# Human_Harp_Player.net
KiCad netlist of a schematic drawn in EAGLE
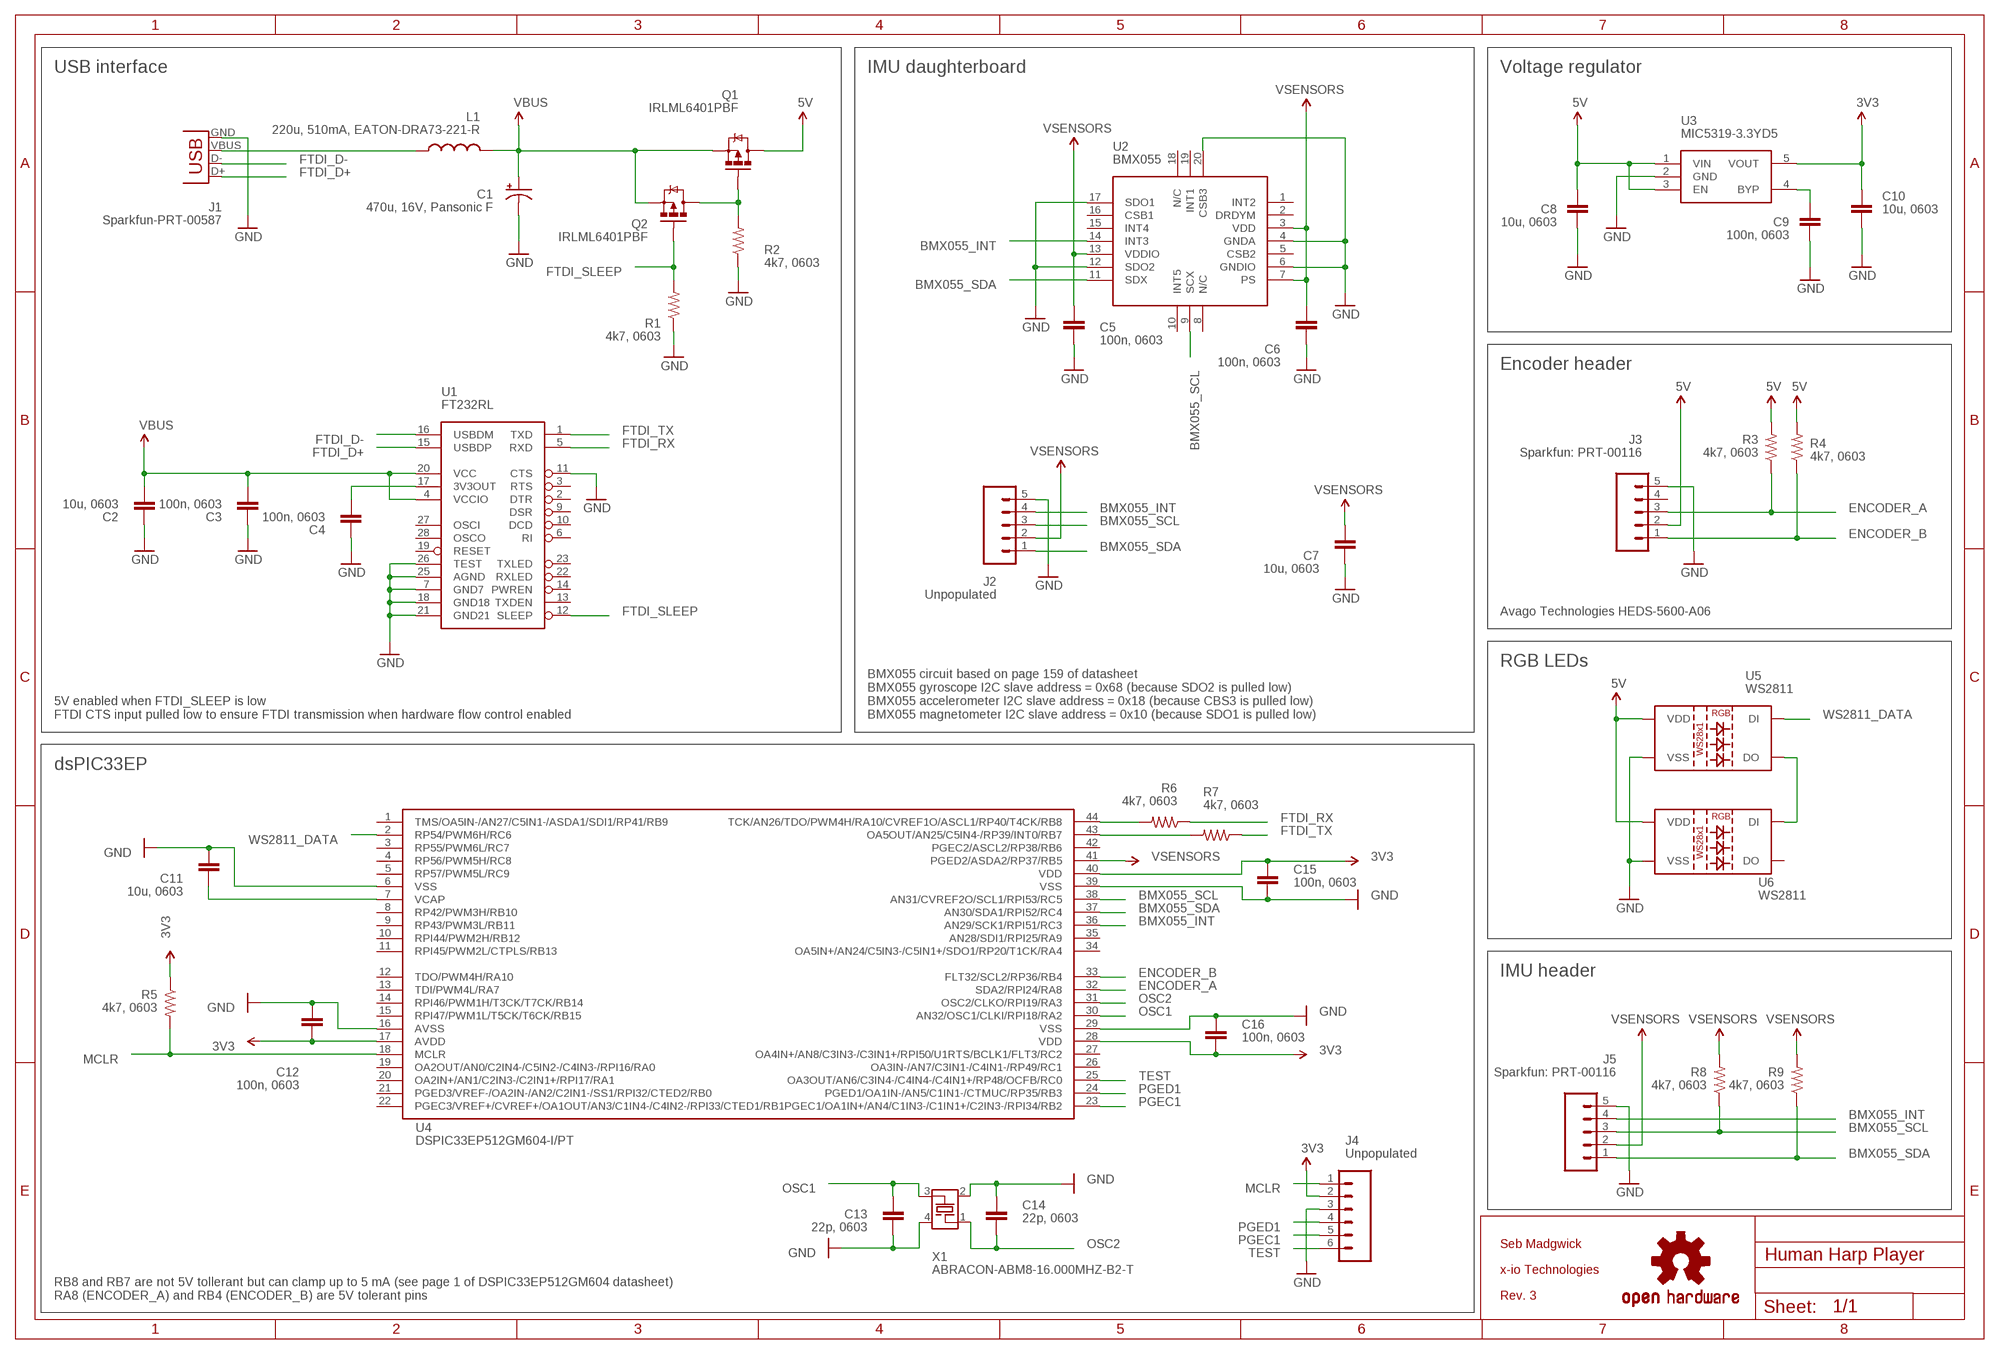
[diagram p0: schematic, sheet 1]

(export (version "E")
  (design (tool "Eeschema 10.0.6"))
  (components
    (comp (ref "C1")
      (value "470u, 16V, Pansonic F")
      (footprint "eagle-import:PANASONIC_F")
      (libsource (lib "eagle-import") (part "CPOL-USF"))
    )
    (comp (ref "C2")
      (value "10u, 0603")
      (footprint "eagle-import:0402-CAP")
      (libsource (lib "eagle-import") (part "CAP0402-CAP"))
    )
    (comp (ref "C3")
      (value "100n, 0603")
      (footprint "eagle-import:0402-CAP")
      (libsource (lib "eagle-import") (part "CAP0402-CAP"))
    )
    (comp (ref "C4")
      (value "100n, 0603")
      (footprint "eagle-import:0402-CAP")
      (libsource (lib "eagle-import") (part "CAP0402-CAP"))
    )
    (comp (ref "C5")
      (value "100n, 0603")
      (footprint "eagle-import:0402-CAP")
      (libsource (lib "eagle-import") (part "CAP0402-CAP"))
    )
    (comp (ref "C6")
      (value "100n, 0603")
      (footprint "eagle-import:0402-CAP")
      (libsource (lib "eagle-import") (part "CAP0402-CAP"))
    )
    (comp (ref "C7")
      (value "10u, 0603")
      (footprint "eagle-import:0402-CAP")
      (libsource (lib "eagle-import") (part "CAP0402-CAP"))
    )
    (comp (ref "C8")
      (value "10u, 0603")
      (footprint "eagle-import:0402-CAP")
      (libsource (lib "eagle-import") (part "CAP0402-CAP"))
    )
    (comp (ref "C9")
      (value "100n, 0603")
      (footprint "eagle-import:0402-CAP")
      (libsource (lib "eagle-import") (part "CAP0402-CAP"))
    )
    (comp (ref "C10")
      (value "10u, 0603")
      (footprint "eagle-import:0402-CAP")
      (libsource (lib "eagle-import") (part "CAP0402-CAP"))
    )
    (comp (ref "C11")
      (value "10u, 0603")
      (footprint "eagle-import:0402-CAP")
      (libsource (lib "eagle-import") (part "CAP0402-CAP"))
    )
    (comp (ref "C12")
      (value "100n, 0603")
      (footprint "eagle-import:0402-CAP")
      (libsource (lib "eagle-import") (part "CAP0402-CAP"))
    )
    (comp (ref "C13")
      (value "22p, 0603")
      (footprint "eagle-import:0402-CAP")
      (libsource (lib "eagle-import") (part "CAP0402-CAP"))
    )
    (comp (ref "C14")
      (value "22p, 0603")
      (footprint "eagle-import:0402-CAP")
      (libsource (lib "eagle-import") (part "CAP0402-CAP"))
    )
    (comp (ref "C15")
      (value "100n, 0603")
      (footprint "eagle-import:0402-CAP")
      (libsource (lib "eagle-import") (part "CAP0402-CAP"))
    )
    (comp (ref "C16")
      (value "100n, 0603")
      (footprint "eagle-import:0402-CAP")
      (libsource (lib "eagle-import") (part "CAP0402-CAP"))
    )
    (comp (ref "J1")
      (value "Sparkfun-PRT-00587")
      (footprint "eagle-import:USB-MINIB")
      (libsource (lib "eagle-import") (part "USBSMD"))
    )
    (comp (ref "J2")
      (value "Unpopulated")
      (footprint "eagle-import:1X05")
      (libsource (lib "eagle-import") (part "M05PTH"))
    )
    (comp (ref "J3")
      (value "Sparkfun: PRT-00116")
      (footprint "eagle-import:1X05")
      (libsource (lib "eagle-import") (part "M05PTH"))
    )
    (comp (ref "J4")
      (value "Unpopulated")
      (footprint "eagle-import:1X06_NO_SILK")
      (libsource (lib "eagle-import") (part "M06NO_SILK"))
    )
    (comp (ref "J5")
      (value "Sparkfun: PRT-00116")
      (footprint "eagle-import:1X05")
      (libsource (lib "eagle-import") (part "M05PTH"))
    )
    (comp (ref "L1")
      (value "220u, 510mA, EATON-DRA73-221-R")
      (footprint "eagle-import:PIS2816")
      (libsource (lib "eagle-import") (part "L-USPIS2816"))
    )
    (comp (ref "LOGO1")
      (value "OSHW-LOGOL")
      (footprint "eagle-import:OSHW-LOGO-L")
      (libsource (lib "eagle-import") (part "OSHW-LOGOL"))
    )
    (comp (ref "Q1")
      (value "IRLML6401PBF")
      (footprint "eagle-import:SOT23-3")
      (libsource (lib "eagle-import") (part "MOSFET-PCHANNEL"))
    )
    (comp (ref "Q2")
      (value "IRLML6401PBF")
      (footprint "eagle-import:SOT23-3")
      (libsource (lib "eagle-import") (part "MOSFET-PCHANNEL"))
    )
    (comp (ref "R1")
      (value "4k7, 0603")
      (footprint "eagle-import:0402-RES")
      (libsource (lib "eagle-import") (part "RESISTOR0402-RES"))
    )
    (comp (ref "R2")
      (value "4k7, 0603")
      (footprint "eagle-import:0402-RES")
      (libsource (lib "eagle-import") (part "RESISTOR0402-RES"))
    )
    (comp (ref "R3")
      (value "4k7, 0603")
      (footprint "eagle-import:0402-RES")
      (libsource (lib "eagle-import") (part "RESISTOR0402-RES"))
    )
    (comp (ref "R4")
      (value "4k7, 0603")
      (footprint "eagle-import:0402-RES")
      (libsource (lib "eagle-import") (part "RESISTOR0402-RES"))
    )
    (comp (ref "R5")
      (value "4k7, 0603")
      (footprint "eagle-import:0402-RES")
      (libsource (lib "eagle-import") (part "RESISTOR0402-RES"))
    )
    (comp (ref "R6")
      (value "4k7, 0603")
      (footprint "eagle-import:0402-RES")
      (libsource (lib "eagle-import") (part "RESISTOR0402-RES"))
    )
    (comp (ref "R7")
      (value "4k7, 0603")
      (footprint "eagle-import:0402-RES")
      (libsource (lib "eagle-import") (part "RESISTOR0402-RES"))
    )
    (comp (ref "R8")
      (value "4k7, 0603")
      (footprint "eagle-import:0402-RES")
      (libsource (lib "eagle-import") (part "RESISTOR0402-RES"))
    )
    (comp (ref "R9")
      (value "4k7, 0603")
      (footprint "eagle-import:0402-RES")
      (libsource (lib "eagle-import") (part "RESISTOR0402-RES"))
    )
    (comp (ref "U1")
      (value "FT232RL")
      (footprint "eagle-import:SSOP28DB")
      (libsource (lib "eagle-import") (part "FT232RLSSOP"))
    )
    (comp (ref "U2")
      (value "BMX055")
      (footprint "eagle-import:BMX055")
      (libsource (lib "eagle-import") (part "BMX055"))
    )
    (comp (ref "U3")
      (value "MIC5319-3.3YD5")
      (footprint "eagle-import:SOT23-5")
      (libsource (lib "eagle-import") (part "MIC5319"))
    )
    (comp (ref "U4")
      (value "DSPIC33EP512GM604-I/PT")
      (footprint "eagle-import:TQFP44")
      (libsource (lib "eagle-import") (part "DSPIC33EP512GM604"))
    )
    (comp (ref "U5")
      (value "WS2811")
      (footprint "eagle-import:LED-TRICOLOR-5050-IC")
      (libsource (lib "eagle-import") (part "LED-TRICOLOR-5050-ICWS2811"))
    )
    (comp (ref "U6")
      (value "WS2811")
      (footprint "eagle-import:LED-TRICOLOR-5050-IC")
      (libsource (lib "eagle-import") (part "LED-TRICOLOR-5050-ICWS2811"))
    )
    (comp (ref "X1")
      (value "ABRACON-ABM8-16.000MHZ-B2-T")
      (footprint "eagle-import:ABM8")
      (libsource (lib "eagle-import") (part "ABM8"))
    )
  )
  (nets
    (net (code "1") (name "/BMX055_INT") (class "Default")
      (node (ref "J2") (pin "4") (pinfunction "4_4") (pintype "passive"))
      (node (ref "J5") (pin "4") (pinfunction "4_4") (pintype "passive"))
      (node (ref "U2") (pin "14") (pinfunction "INT3_14") (pintype "bidirectional"))
      (node (ref "U4") (pin "36") (pinfunction "AN29/SCK1/RPI51/RC3_36") (pintype "bidirectional"))
    )
    (net (code "2") (name "/BMX055_SCL") (class "Default")
      (node (ref "J2") (pin "3") (pinfunction "3_3") (pintype "passive"))
      (node (ref "J5") (pin "3") (pinfunction "3_3") (pintype "passive"))
      (node (ref "R8") (pin "1") (pinfunction "1_1") (pintype "passive"))
      (node (ref "U2") (pin "9") (pinfunction "SCX_9") (pintype "bidirectional"))
      (node (ref "U4") (pin "38") (pinfunction "AN31/CVREF2O/SCL1/RPI53/RC5_38") (pintype "bidirectional"))
    )
    (net (code "3") (name "/BMX055_SDA") (class "Default")
      (node (ref "J2") (pin "1") (pinfunction "1_1") (pintype "passive"))
      (node (ref "J5") (pin "1") (pinfunction "1_1") (pintype "passive"))
      (node (ref "R9") (pin "1") (pinfunction "1_1") (pintype "passive"))
      (node (ref "U2") (pin "11") (pinfunction "SDX_11") (pintype "bidirectional"))
      (node (ref "U4") (pin "37") (pinfunction "AN30/SDA1/RPI52/RC4_37") (pintype "bidirectional"))
    )
    (net (code "4") (name "/ENCODER_A") (class "Default")
      (node (ref "J3") (pin "3") (pinfunction "3_3") (pintype "passive"))
      (node (ref "R3") (pin "1") (pinfunction "1_1") (pintype "passive"))
      (node (ref "U4") (pin "32") (pinfunction "SDA2/RPI24/RA8_32") (pintype "bidirectional"))
    )
    (net (code "5") (name "/ENCODER_B") (class "Default")
      (node (ref "J3") (pin "1") (pinfunction "1_1") (pintype "passive"))
      (node (ref "R4") (pin "1") (pinfunction "1_1") (pintype "passive"))
      (node (ref "U4") (pin "33") (pinfunction "FLT32/SCL2/RP36/RB4_33") (pintype "bidirectional"))
    )
    (net (code "6") (name "/FTDI_D+") (class "Default")
      (node (ref "J1") (pin "D+") (pinfunction "D+_D+") (pintype "bidirectional"))
      (node (ref "U1") (pin "15") (pinfunction "USBDP_15") (pintype "bidirectional"))
    )
    (net (code "7") (name "/FTDI_D-") (class "Default")
      (node (ref "J1") (pin "D-") (pinfunction "D-_D-") (pintype "bidirectional"))
      (node (ref "U1") (pin "16") (pinfunction "USBDM_16") (pintype "bidirectional"))
    )
    (net (code "8") (name "/FTDI_RX") (class "Default")
      (node (ref "R6") (pin "1") (pinfunction "1_1") (pintype "passive"))
      (node (ref "U1") (pin "5") (pinfunction "RXD_5") (pintype "input"))
    )
    (net (code "9") (name "/FTDI_SLEEP") (class "Default")
      (node (ref "Q2") (pin "1") (pinfunction "G_1") (pintype "passive"))
      (node (ref "R1") (pin "2") (pinfunction "2_2") (pintype "passive"))
      (node (ref "U1") (pin "12") (pinfunction "SLEEP_12") (pintype "input"))
    )
    (net (code "10") (name "/FTDI_TX") (class "Default")
      (node (ref "R7") (pin "1") (pinfunction "1_1") (pintype "passive"))
      (node (ref "U1") (pin "1") (pinfunction "TXD_1") (pintype "output"))
    )
    (net (code "11") (name "/MCLR") (class "Default")
      (node (ref "J4") (pin "1") (pinfunction "1_1") (pintype "passive"))
      (node (ref "R5") (pin "2") (pinfunction "2_2") (pintype "passive"))
      (node (ref "U4") (pin "18") (pinfunction "MCLR_18") (pintype "bidirectional"))
    )
    (net (code "12") (name "/OSC1") (class "Default")
      (node (ref "C13") (pin "2") (pinfunction "2_2") (pintype "passive"))
      (node (ref "U4") (pin "30") (pinfunction "AN32/OSC1/CLKI/RPI18/RA2_30") (pintype "bidirectional"))
      (node (ref "X1") (pin "3") (pintype "bidirectional"))
    )
    (net (code "13") (name "/OSC2") (class "Default")
      (node (ref "C14") (pin "2") (pinfunction "2_2") (pintype "passive"))
      (node (ref "U4") (pin "31") (pinfunction "OSC2/CLKO/RPI19/RA3_31") (pintype "bidirectional"))
      (node (ref "X1") (pin "1") (pintype "bidirectional"))
    )
    (net (code "14") (name "/PGEC1") (class "Default")
      (node (ref "J4") (pin "5") (pinfunction "5_5") (pintype "passive"))
      (node (ref "U4") (pin "23") (pinfunction "PGEC1/OA1IN+/AN4/C1IN3-/C1IN1+/C2IN3-/RPI34/RB2_23") (pintype "bidirectional"))
    )
    (net (code "15") (name "/PGED1") (class "Default")
      (node (ref "J4") (pin "4") (pinfunction "4_4") (pintype "passive"))
      (node (ref "U4") (pin "24") (pinfunction "PGED1/OA1IN-/AN5/C1IN1-/CTMUC/RP35/RB3_24") (pintype "bidirectional"))
    )
    (net (code "16") (name "/TEST") (class "Default")
      (node (ref "J4") (pin "6") (pinfunction "6_6") (pintype "passive"))
      (node (ref "U4") (pin "25") (pinfunction "OA3OUT/AN6/C3IN4-/C4IN4-/C4IN1+/RP48/OCFB/RC0_25") (pintype "bidirectional"))
    )
    (net (code "17") (name "/WS2811_DATA") (class "Default")
      (node (ref "U4") (pin "2") (pinfunction "RP54/PWM6H/RC6_2") (pintype "bidirectional"))
      (node (ref "U5") (pin "2") (pinfunction "DI_2") (pintype "bidirectional"))
    )
    (net (code "18") (name "3V3") (class "Default")
      (node (ref "C10") (pin "1") (pinfunction "1_1") (pintype "passive"))
      (node (ref "C12") (pin "1") (pinfunction "1_1") (pintype "passive"))
      (node (ref "C15") (pin "1") (pinfunction "1_1") (pintype "passive"))
      (node (ref "C16") (pin "2") (pinfunction "2_2") (pintype "passive"))
      (node (ref "J4") (pin "2") (pinfunction "2_2") (pintype "passive"))
      (node (ref "R5") (pin "1") (pinfunction "1_1") (pintype "passive"))
      (node (ref "U3") (pin "5") (pinfunction "VOUT_5") (pintype "bidirectional"))
      (node (ref "U4") (pin "17") (pinfunction "AVDD_17") (pintype "bidirectional"))
      (node (ref "U4") (pin "28") (pinfunction "VDD_28") (pintype "bidirectional"))
      (node (ref "U4") (pin "40") (pinfunction "VDD_40") (pintype "bidirectional"))
    )
    (net (code "19") (name "5V") (class "Default")
      (node (ref "C8") (pin "1") (pinfunction "1_1") (pintype "passive"))
      (node (ref "J3") (pin "2") (pinfunction "2_2") (pintype "passive"))
      (node (ref "Q1") (pin "3") (pinfunction "D_3") (pintype "passive"))
      (node (ref "R3") (pin "2") (pinfunction "2_2") (pintype "passive"))
      (node (ref "R4") (pin "2") (pinfunction "2_2") (pintype "passive"))
      (node (ref "U3") (pin "1") (pinfunction "VIN_1") (pintype "bidirectional"))
      (node (ref "U3") (pin "3") (pinfunction "EN_3") (pintype "bidirectional"))
      (node (ref "U5") (pin "3") (pinfunction "VDD_3") (pintype "bidirectional"))
      (node (ref "U5") (pin "5") (pinfunction "VDD_5") (pintype "bidirectional"))
      (node (ref "U6") (pin "3") (pinfunction "VDD_3") (pintype "bidirectional"))
      (node (ref "U6") (pin "5") (pinfunction "VDD_5") (pintype "bidirectional"))
    )
    (net (code "20") (name "GND") (class "Default")
      (node (ref "C1") (pin "-") (pinfunction "-_-") (pintype "passive"))
      (node (ref "C10") (pin "2") (pinfunction "2_2") (pintype "passive"))
      (node (ref "C11") (pin "2") (pinfunction "2_2") (pintype "passive"))
      (node (ref "C12") (pin "2") (pinfunction "2_2") (pintype "passive"))
      (node (ref "C13") (pin "1") (pinfunction "1_1") (pintype "passive"))
      (node (ref "C14") (pin "1") (pinfunction "1_1") (pintype "passive"))
      (node (ref "C15") (pin "2") (pinfunction "2_2") (pintype "passive"))
      (node (ref "C16") (pin "1") (pinfunction "1_1") (pintype "passive"))
      (node (ref "C2") (pin "1") (pinfunction "1_1") (pintype "passive"))
      (node (ref "C3") (pin "1") (pinfunction "1_1") (pintype "passive"))
      (node (ref "C4") (pin "1") (pinfunction "1_1") (pintype "passive"))
      (node (ref "C5") (pin "2") (pinfunction "2_2") (pintype "passive"))
      (node (ref "C6") (pin "2") (pinfunction "2_2") (pintype "passive"))
      (node (ref "C7") (pin "1") (pinfunction "1_1") (pintype "passive"))
      (node (ref "C8") (pin "2") (pinfunction "2_2") (pintype "passive"))
      (node (ref "C9") (pin "2") (pinfunction "2_2") (pintype "passive"))
      (node (ref "J1") (pin "GND") (pinfunction "GND_GND") (pintype "bidirectional"))
      (node (ref "J2") (pin "5") (pinfunction "5_5") (pintype "passive"))
      (node (ref "J3") (pin "5") (pinfunction "5_5") (pintype "passive"))
      (node (ref "J4") (pin "3") (pinfunction "3_3") (pintype "passive"))
      (node (ref "J5") (pin "5") (pinfunction "5_5") (pintype "passive"))
      (node (ref "R1") (pin "1") (pinfunction "1_1") (pintype "passive"))
      (node (ref "R2") (pin "1") (pinfunction "1_1") (pintype "passive"))
      (node (ref "U1") (pin "11") (pinfunction "CTS_11") (pintype "input"))
      (node (ref "U1") (pin "18") (pinfunction "GND18_18") (pintype "power_in"))
      (node (ref "U1") (pin "21") (pinfunction "GND21_21") (pintype "power_in"))
      (node (ref "U1") (pin "25") (pinfunction "AGND_25") (pintype "power_in"))
      (node (ref "U1") (pin "26") (pinfunction "TEST_26") (pintype "input"))
      (node (ref "U1") (pin "7") (pinfunction "GND7_7") (pintype "power_in"))
      (node (ref "U2") (pin "12") (pinfunction "SDO2_12") (pintype "bidirectional"))
      (node (ref "U2") (pin "17") (pinfunction "SDO1_17") (pintype "bidirectional"))
      (node (ref "U2") (pin "20") (pinfunction "CSB3_20") (pintype "bidirectional"))
      (node (ref "U2") (pin "4") (pinfunction "GNDA_4") (pintype "bidirectional"))
      (node (ref "U2") (pin "6") (pinfunction "GNDIO_6") (pintype "bidirectional"))
      (node (ref "U3") (pin "2") (pinfunction "GND_2") (pintype "bidirectional"))
      (node (ref "U4") (pin "16") (pinfunction "AVSS_16") (pintype "bidirectional"))
      (node (ref "U4") (pin "29") (pinfunction "VSS_29") (pintype "bidirectional"))
      (node (ref "U4") (pin "39") (pinfunction "VSS_39") (pintype "bidirectional"))
      (node (ref "U4") (pin "6") (pinfunction "VSS_6") (pintype "bidirectional"))
      (node (ref "U5") (pin "6") (pinfunction "VSS_6") (pintype "bidirectional"))
      (node (ref "U6") (pin "6") (pinfunction "VSS_6") (pintype "bidirectional"))
      (node (ref "X1") (pin "2") (pintype "bidirectional"))
      (node (ref "X1") (pin "4") (pintype "bidirectional"))
    )
    (net (code "21") (name "Net-(J1-PadVBUS)") (class "Default")
      (node (ref "J1") (pin "VBUS") (pinfunction "VBUS_VBUS") (pintype "bidirectional"))
      (node (ref "L1") (pin "1") (pinfunction "1_1") (pintype "passive"))
    )
    (net (code "22") (name "Net-(Q1-G)") (class "Default")
      (node (ref "Q1") (pin "1") (pinfunction "G_1") (pintype "passive"))
      (node (ref "Q2") (pin "3") (pinfunction "D_3") (pintype "passive"))
      (node (ref "R2") (pin "2") (pinfunction "2_2") (pintype "passive"))
    )
    (net (code "23") (name "Net-(U1-3V3OUT)") (class "Default")
      (node (ref "C4") (pin "2") (pinfunction "2_2") (pintype "passive"))
      (node (ref "U1") (pin "17") (pinfunction "3V3OUT_17") (pintype "output"))
    )
    (net (code "24") (name "Net-(U3-BYP)") (class "Default")
      (node (ref "C9") (pin "1") (pinfunction "1_1") (pintype "passive"))
      (node (ref "U3") (pin "4") (pinfunction "BYP_4") (pintype "bidirectional"))
    )
    (net (code "25") (name "Net-(U4-OA5OUT{slash}AN25{slash}C5IN4-{slash}RP39{slash}INT0{slash}RB7)") (class "Default")
      (node (ref "R7") (pin "2") (pinfunction "2_2") (pintype "passive"))
      (node (ref "U4") (pin "43") (pinfunction "OA5OUT/AN25/C5IN4-/RP39/INT0/RB7_43") (pintype "bidirectional"))
    )
    (net (code "26") (name "Net-(U4-TCK{slash}AN26{slash}TDO{slash}PWM4H{slash}RA10{slash}CVREF1O{slash}ASCL1{slash}RP40{slash}T4CK{slash}RB8)") (class "Default")
      (node (ref "R6") (pin "2") (pinfunction "2_2") (pintype "passive"))
      (node (ref "U4") (pin "44") (pinfunction "TCK/AN26/TDO/PWM4H/RA10/CVREF1O/ASCL1/RP40/T4CK/RB8_44") (pintype "bidirectional"))
    )
    (net (code "27") (name "Net-(U4-VCAP)") (class "Default")
      (node (ref "C11") (pin "1") (pinfunction "1_1") (pintype "passive"))
      (node (ref "U4") (pin "7") (pinfunction "VCAP_7") (pintype "bidirectional"))
    )
    (net (code "28") (name "Net-(U5-DO)") (class "Default")
      (node (ref "U5") (pin "1") (pinfunction "DO_1") (pintype "bidirectional"))
      (node (ref "U6") (pin "2") (pinfunction "DI_2") (pintype "bidirectional"))
    )
    (net (code "29") (name "VBUS") (class "Default")
      (node (ref "C1") (pin "+") (pinfunction "+_+") (pintype "passive"))
      (node (ref "C2") (pin "2") (pinfunction "2_2") (pintype "passive"))
      (node (ref "C3") (pin "2") (pinfunction "2_2") (pintype "passive"))
      (node (ref "L1") (pin "2") (pinfunction "2_2") (pintype "passive"))
      (node (ref "Q1") (pin "2") (pinfunction "S_2") (pintype "passive"))
      (node (ref "Q2") (pin "2") (pinfunction "S_2") (pintype "passive"))
      (node (ref "U1") (pin "20") (pinfunction "VCC_20") (pintype "power_in"))
      (node (ref "U1") (pin "4") (pinfunction "VCCIO_4") (pintype "power_in"))
    )
    (net (code "30") (name "VSENSORS") (class "Default")
      (node (ref "C5") (pin "1") (pinfunction "1_1") (pintype "passive"))
      (node (ref "C6") (pin "1") (pinfunction "1_1") (pintype "passive"))
      (node (ref "C7") (pin "2") (pinfunction "2_2") (pintype "passive"))
      (node (ref "J2") (pin "2") (pinfunction "2_2") (pintype "passive"))
      (node (ref "J5") (pin "2") (pinfunction "2_2") (pintype "passive"))
      (node (ref "R8") (pin "2") (pinfunction "2_2") (pintype "passive"))
      (node (ref "R9") (pin "2") (pinfunction "2_2") (pintype "passive"))
      (node (ref "U2") (pin "13") (pinfunction "VDDIO_13") (pintype "bidirectional"))
      (node (ref "U2") (pin "3") (pinfunction "VDD_3") (pintype "bidirectional"))
      (node (ref "U2") (pin "7") (pinfunction "PS_7") (pintype "bidirectional"))
      (node (ref "U4") (pin "41") (pinfunction "PGED2/ASDA2/RP37/RB5_41") (pintype "bidirectional"))
    )
    (net (code "31") (name "unconnected-(J3-Pad4)") (class "Default")
      (node (ref "J3") (pin "4") (pinfunction "4_4") (pintype "passive"))
    )
    (net (code "32") (name "unconnected-(U1-DCD-Pad10)") (class "Default")
      (node (ref "U1") (pin "10") (pinfunction "DCD_10") (pintype "input"))
    )
    (net (code "33") (name "unconnected-(U1-DSR-Pad9)") (class "Default")
      (node (ref "U1") (pin "9") (pinfunction "DSR_9") (pintype "input"))
    )
    (net (code "34") (name "unconnected-(U1-DTR-Pad2)") (class "Default")
      (node (ref "U1") (pin "2") (pinfunction "DTR_2") (pintype "output"))
    )
    (net (code "35") (name "unconnected-(U1-OSCI-Pad27)") (class "Default")
      (node (ref "U1") (pin "27") (pinfunction "OSCI_27") (pintype "input"))
    )
    (net (code "36") (name "unconnected-(U1-OSCO-Pad28)") (class "Default")
      (node (ref "U1") (pin "28") (pinfunction "OSCO_28") (pintype "output"))
    )
    (net (code "37") (name "unconnected-(U1-PWREN-Pad14)") (class "Default")
      (node (ref "U1") (pin "14") (pinfunction "PWREN_14") (pintype "input"))
    )
    (net (code "38") (name "unconnected-(U1-RESET-Pad19)") (class "Default")
      (node (ref "U1") (pin "19") (pinfunction "RESET_19") (pintype "input"))
    )
    (net (code "39") (name "unconnected-(U1-RI-Pad6)") (class "Default")
      (node (ref "U1") (pin "6") (pinfunction "RI_6") (pintype "input"))
    )
    (net (code "40") (name "unconnected-(U1-RTS-Pad3)") (class "Default")
      (node (ref "U1") (pin "3") (pinfunction "RTS_3") (pintype "output"))
    )
    (net (code "41") (name "unconnected-(U1-RXLED-Pad22)") (class "Default")
      (node (ref "U1") (pin "22") (pinfunction "RXLED_22") (pintype "input"))
    )
    (net (code "42") (name "unconnected-(U1-TXDEN-Pad13)") (class "Default")
      (node (ref "U1") (pin "13") (pinfunction "TXDEN_13") (pintype "input"))
    )
    (net (code "43") (name "unconnected-(U1-TXLED-Pad23)") (class "Default")
      (node (ref "U1") (pin "23") (pinfunction "TXLED_23") (pintype "input"))
    )
    (net (code "44") (name "unconnected-(U2-CSB1-Pad16)") (class "Default")
      (node (ref "U2") (pin "16") (pinfunction "CSB1_16") (pintype "bidirectional"))
    )
    (net (code "45") (name "unconnected-(U2-CSB2-Pad5)") (class "Default")
      (node (ref "U2") (pin "5") (pinfunction "CSB2_5") (pintype "bidirectional"))
    )
    (net (code "46") (name "unconnected-(U2-DRDYM-Pad2)") (class "Default")
      (node (ref "U2") (pin "2") (pinfunction "DRDYM_2") (pintype "bidirectional"))
    )
    (net (code "47") (name "unconnected-(U2-INT1-Pad19)") (class "Default")
      (node (ref "U2") (pin "19") (pinfunction "INT1_19") (pintype "bidirectional"))
    )
    (net (code "48") (name "unconnected-(U2-INT2-Pad1)") (class "Default")
      (node (ref "U2") (pin "1") (pinfunction "INT2_1") (pintype "bidirectional"))
    )
    (net (code "49") (name "unconnected-(U2-INT4-Pad15)") (class "Default")
      (node (ref "U2") (pin "15") (pinfunction "INT4_15") (pintype "bidirectional"))
    )
    (net (code "50") (name "unconnected-(U2-INT5-Pad10)") (class "Default")
      (node (ref "U2") (pin "10") (pinfunction "INT5_10") (pintype "bidirectional"))
    )
    (net (code "51") (name "unconnected-(U2-N{slash}C-Pad8)") (class "Default")
      (node (ref "U2") (pin "8") (pinfunction "N/C_8") (pintype "bidirectional"))
    )
    (net (code "52") (name "unconnected-(U2-N{slash}C-Pad18)") (class "Default")
      (node (ref "U2") (pin "18") (pinfunction "N/C_18") (pintype "bidirectional"))
    )
    (net (code "53") (name "unconnected-(U4-AN28{slash}SDI1{slash}RPI25{slash}RA9-Pad35)") (class "Default")
      (node (ref "U4") (pin "35") (pinfunction "AN28/SDI1/RPI25/RA9_35") (pintype "bidirectional"))
    )
    (net (code "54") (name "unconnected-(U4-OA2IN+{slash}AN1{slash}C2IN3-{slash}C2IN1+{slash}RPI17{slash}RA1-Pad20)") (class "Default")
      (node (ref "U4") (pin "20") (pinfunction "OA2IN+/AN1/C2IN3-/C2IN1+/RPI17/RA1_20") (pintype "bidirectional"))
    )
    (net (code "55") (name "unconnected-(U4-OA2OUT{slash}AN0{slash}C2IN4-{slash}C5IN2-{slash}C4IN3-{slash}RPI16{slash}RA0-Pad19)") (class "Default")
      (node (ref "U4") (pin "19") (pinfunction "OA2OUT/AN0/C2IN4-/C5IN2-/C4IN3-/RPI16/RA0_19") (pintype "bidirectional"))
    )
    (net (code "56") (name "unconnected-(U4-OA3IN-{slash}AN7{slash}C3IN1-{slash}C4IN1-{slash}RP49{slash}RC1-Pad26)") (class "Default")
      (node (ref "U4") (pin "26") (pinfunction "OA3IN-/AN7/C3IN1-/C4IN1-/RP49/RC1_26") (pintype "bidirectional"))
    )
    (net (code "57") (name "unconnected-(U4-OA4IN+{slash}AN8{slash}C3IN3-{slash}C3IN1+{slash}RPI50{slash}U1RTS{slash}BCLK1{slash}FLT3{slash}RC2-Pad27)") (class "Default")
      (node (ref "U4") (pin "27") (pinfunction "OA4IN+/AN8/C3IN3-/C3IN1+/RPI50/U1RTS/BCLK1/FLT3/RC2_27") (pintype "bidirectional"))
    )
    (net (code "58") (name "unconnected-(U4-OA5IN+{slash}AN24{slash}C5IN3-{slash}C5IN1+{slash}SDO1{slash}RP20{slash}T1CK{slash}RA4-Pad34)") (class "Default")
      (node (ref "U4") (pin "34") (pinfunction "OA5IN+/AN24/C5IN3-/C5IN1+/SDO1/RP20/T1CK/RA4_34") (pintype "bidirectional"))
    )
    (net (code "59") (name "unconnected-(U4-PGEC2{slash}ASCL2{slash}RP38{slash}RB6-Pad42)") (class "Default")
      (node (ref "U4") (pin "42") (pinfunction "PGEC2/ASCL2/RP38/RB6_42") (pintype "bidirectional"))
    )
    (net (code "60") (name "unconnected-(U4-PGEC3{slash}VREF+{slash}CVREF+{slash}OA1OUT{slash}AN3{slash}C1IN4-{slash}C4IN2-{slash}RPI33{slash}CTED1{slash}RB1-Pad22)") (class "Default")
      (node (ref "U4") (pin "22") (pinfunction "PGEC3/VREF+/CVREF+/OA1OUT/AN3/C1IN4-/C4IN2-/RPI33/CTED1/RB1_22") (pintype "bidirectional"))
    )
    (net (code "61") (name "unconnected-(U4-PGED3{slash}VREF-{slash}OA2IN-{slash}AN2{slash}C2IN1-{slash}SS1{slash}RPI32{slash}CTED2{slash}RB0-Pad21)") (class "Default")
      (node (ref "U4") (pin "21") (pinfunction "PGED3/VREF-/OA2IN-/AN2/C2IN1-/SS1/RPI32/CTED2/RB0_21") (pintype "bidirectional"))
    )
    (net (code "62") (name "unconnected-(U4-RP42{slash}PWM3H{slash}RB10-Pad8)") (class "Default")
      (node (ref "U4") (pin "8") (pinfunction "RP42/PWM3H/RB10_8") (pintype "bidirectional"))
    )
    (net (code "63") (name "unconnected-(U4-RP43{slash}PWM3L{slash}RB11-Pad9)") (class "Default")
      (node (ref "U4") (pin "9") (pinfunction "RP43/PWM3L/RB11_9") (pintype "bidirectional"))
    )
    (net (code "64") (name "unconnected-(U4-RP55{slash}PWM6L{slash}RC7-Pad3)") (class "Default")
      (node (ref "U4") (pin "3") (pinfunction "RP55/PWM6L/RC7_3") (pintype "bidirectional"))
    )
    (net (code "65") (name "unconnected-(U4-RP56{slash}PWM5H{slash}RC8-Pad4)") (class "Default")
      (node (ref "U4") (pin "4") (pinfunction "RP56/PWM5H/RC8_4") (pintype "bidirectional"))
    )
    (net (code "66") (name "unconnected-(U4-RP57{slash}PWM5L{slash}RC9-Pad5)") (class "Default")
      (node (ref "U4") (pin "5") (pinfunction "RP57/PWM5L/RC9_5") (pintype "bidirectional"))
    )
    (net (code "67") (name "unconnected-(U4-RPI44{slash}PWM2H{slash}RB12-Pad10)") (class "Default")
      (node (ref "U4") (pin "10") (pinfunction "RPI44/PWM2H/RB12_10") (pintype "bidirectional"))
    )
    (net (code "68") (name "unconnected-(U4-RPI45{slash}PWM2L{slash}CTPLS{slash}RB13-Pad11)") (class "Default")
      (node (ref "U4") (pin "11") (pinfunction "RPI45/PWM2L/CTPLS/RB13_11") (pintype "bidirectional"))
    )
    (net (code "69") (name "unconnected-(U4-RPI46{slash}PWM1H{slash}T3CK{slash}T7CK{slash}RB14-Pad14)") (class "Default")
      (node (ref "U4") (pin "14") (pinfunction "RPI46/PWM1H/T3CK/T7CK/RB14_14") (pintype "bidirectional"))
    )
    (net (code "70") (name "unconnected-(U4-RPI47{slash}PWM1L{slash}T5CK{slash}T6CK{slash}RB15-Pad15)") (class "Default")
      (node (ref "U4") (pin "15") (pinfunction "RPI47/PWM1L/T5CK/T6CK/RB15_15") (pintype "bidirectional"))
    )
    (net (code "71") (name "unconnected-(U4-TDI{slash}PWM4L{slash}RA7-Pad13)") (class "Default")
      (node (ref "U4") (pin "13") (pinfunction "TDI/PWM4L/RA7_13") (pintype "bidirectional"))
    )
    (net (code "72") (name "unconnected-(U4-TDO{slash}PWM4H{slash}RA10-Pad12)") (class "Default")
      (node (ref "U4") (pin "12") (pinfunction "TDO/PWM4H/RA10_12") (pintype "bidirectional"))
    )
    (net (code "73") (name "unconnected-(U4-TMS{slash}OA5IN-{slash}AN27{slash}C5IN1-{slash}ASDA1{slash}SDI1{slash}RP41{slash}RB9-Pad1)") (class "Default")
      (node (ref "U4") (pin "1") (pinfunction "TMS/OA5IN-/AN27/C5IN1-/ASDA1/SDI1/RP41/RB9_1") (pintype "bidirectional"))
    )
    (net (code "74") (name "unconnected-(U6-DO-Pad1)") (class "Default")
      (node (ref "U6") (pin "1") (pinfunction "DO_1") (pintype "bidirectional"))
    )
  )
)
